# Sheet_1.net
KiCad netlist of a schematic drawn in EasyEDA
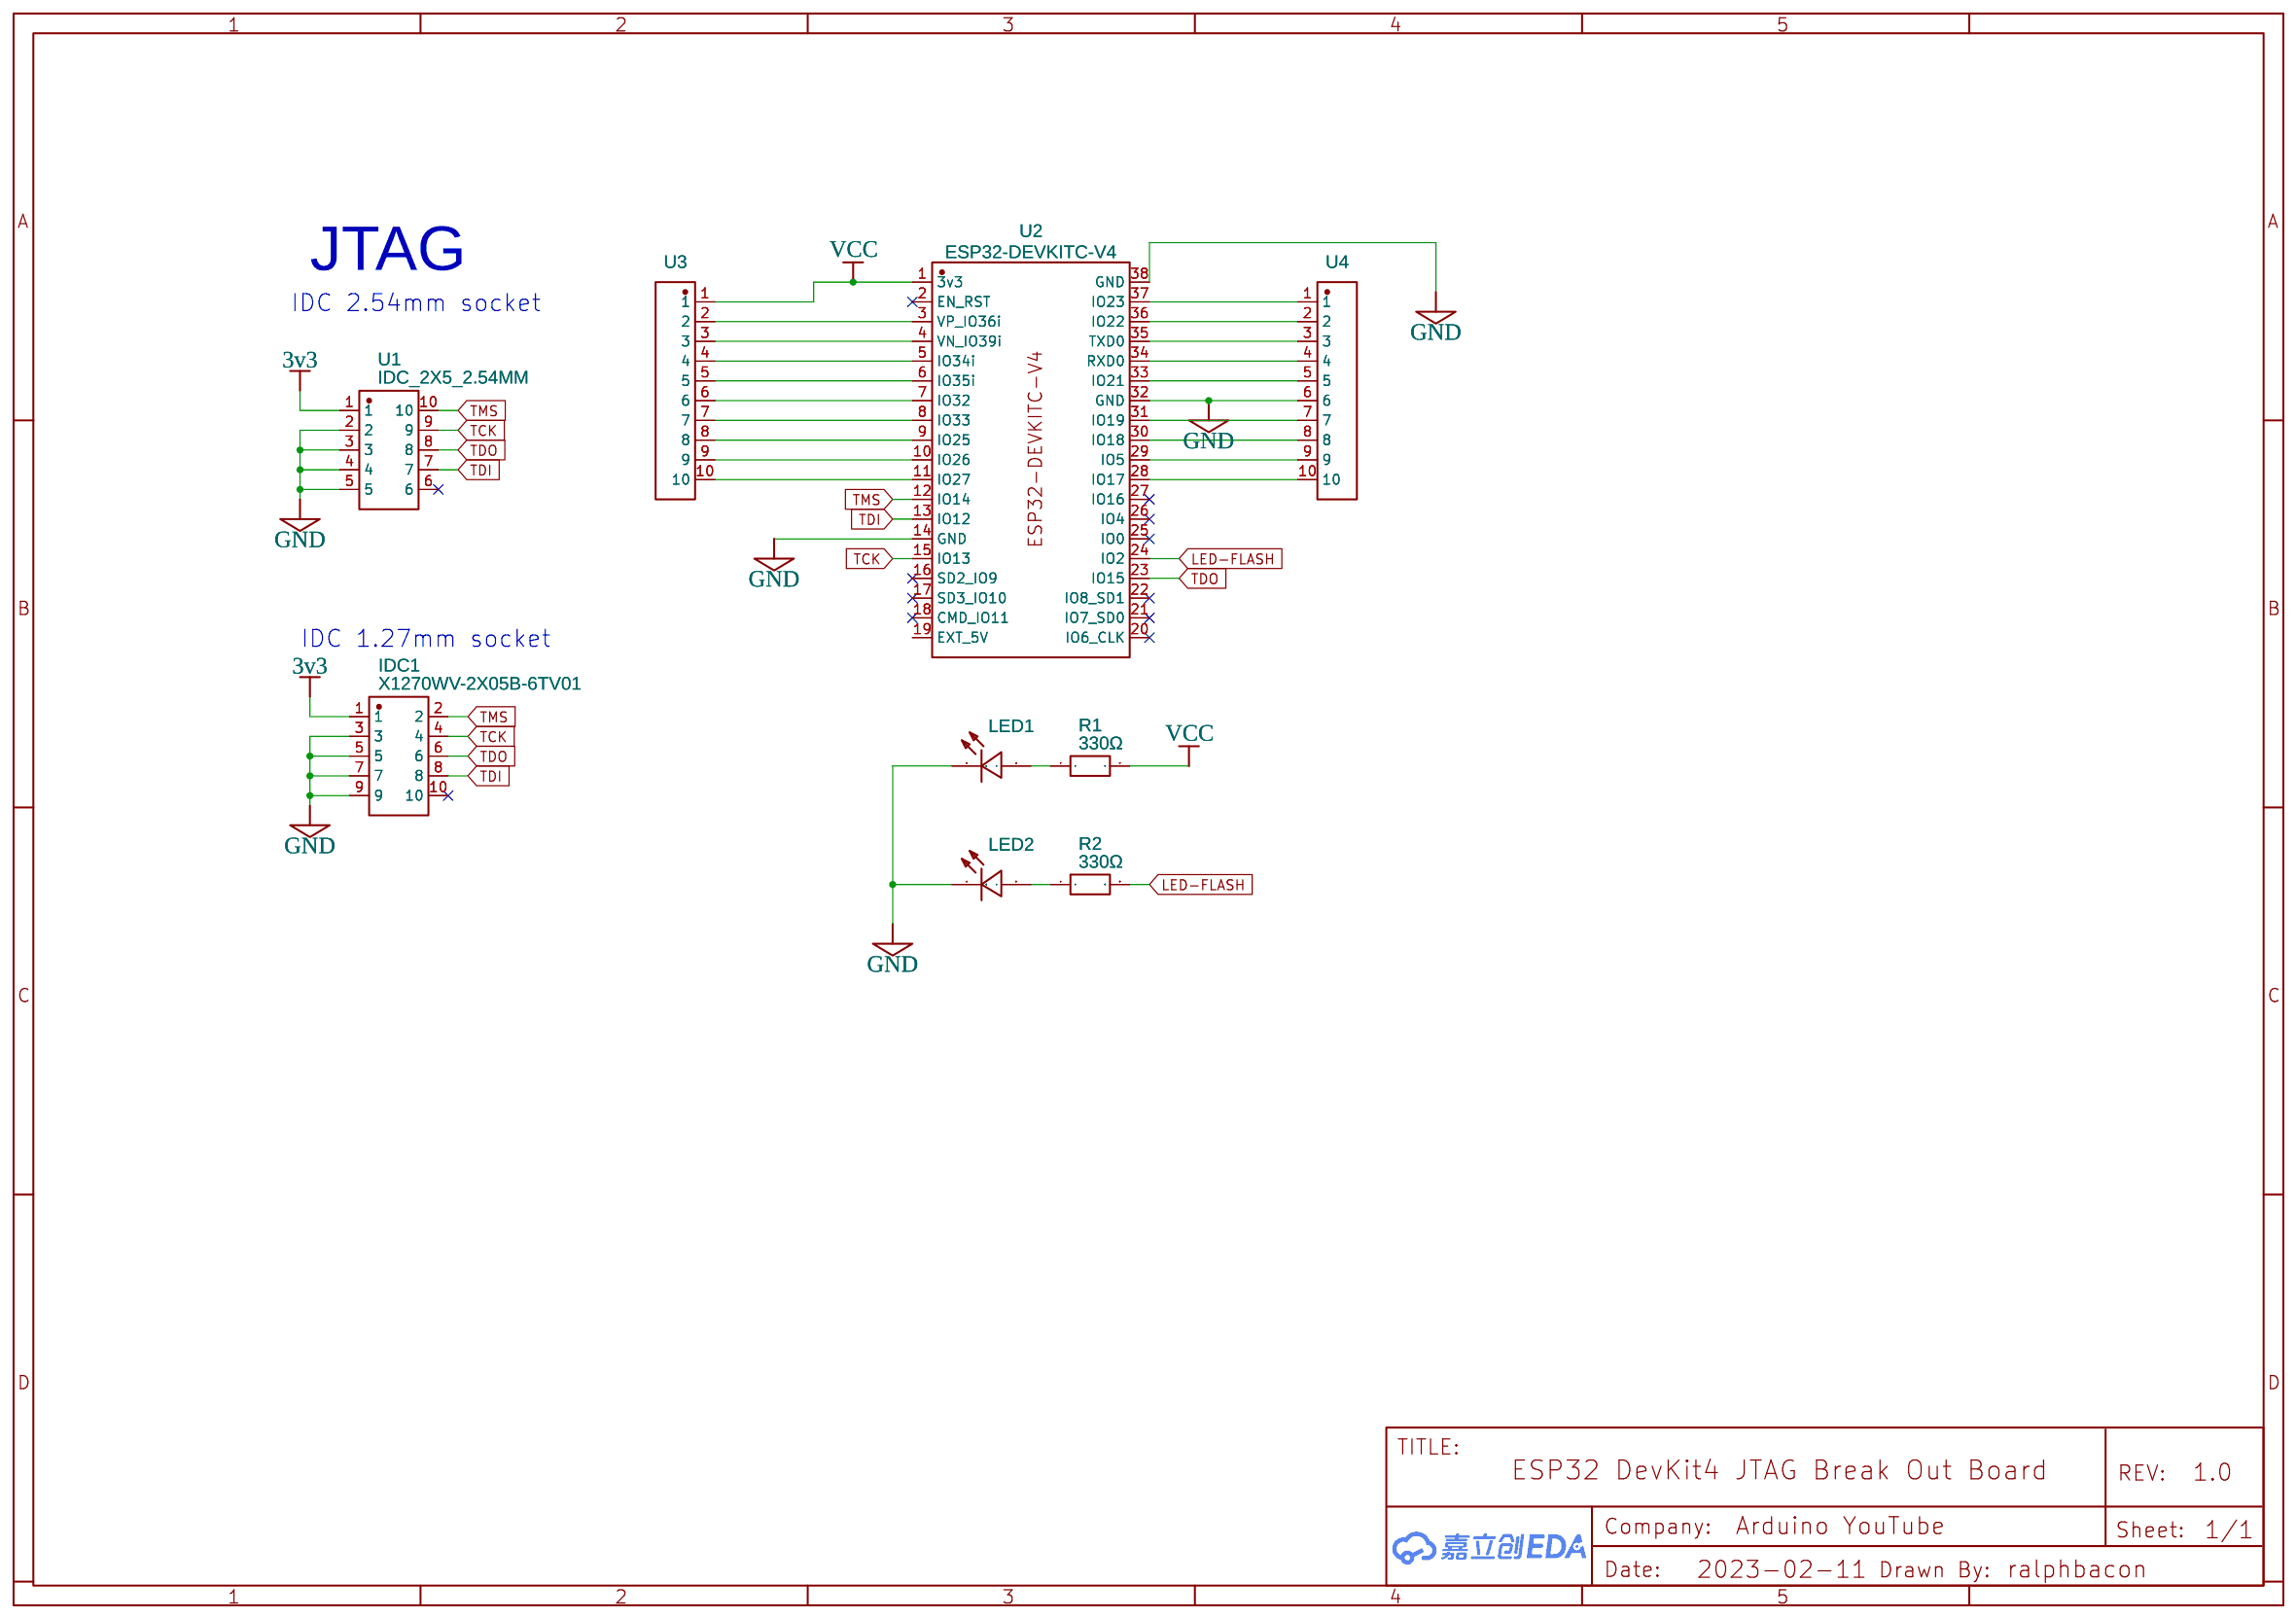
[diagram p0: schematic sheet]

(export (version "E")
  (design (tool "Eeschema 10.0.6"))
  (components
    (comp (ref "IDC1")
      (value "X1270WV-2X05B-6TV01")
      (fields
        (field (name "BOM_Manufacturer Part") "X1270WV-2x05B-6TV01")
        (field (name "BOM_Supplier Part") "C2962225")
      )
      (libsource (lib "") (part "X1270WV-2X05B-6TV01"))
    )
    (comp (ref "LED1")
      (value "SMDREDLED红色超高亮0805")
      (fields
        (field (name "BOM_Manufacturer Part") "SMDRedLED红色超高亮0805")
        (field (name "BOM_Supplier Part") "C9900019100")
      )
      (libsource (lib "") (part "SMDREDLED红色超高亮0805"))
    )
    (comp (ref "LED2")
      (value "SMDREDLED红色超高亮0805")
      (fields
        (field (name "BOM_Manufacturer Part") "SMDRedLED红色超高亮0805")
        (field (name "BOM_Supplier Part") "C9900019100")
      )
      (libsource (lib "") (part "SMDREDLED红色超高亮0805"))
    )
    (comp (ref "R1")
      (value "330Ω")
      (fields
        (field (name "BOM_Manufacturer Part") "RT0603DRD07330RL")
        (field (name "BOM_Supplier Part") "C723588")
      )
      (libsource (lib "") (part "RT0603DRD07330RL"))
    )
    (comp (ref "R2")
      (value "330Ω")
      (fields
        (field (name "BOM_Manufacturer Part") "RT0603DRD07330RL")
        (field (name "BOM_Supplier Part") "C723588")
      )
      (libsource (lib "") (part "RT0603DRD07330RL"))
    )
    (comp (ref "U1")
      (value "IDC_2X5_2.54MM")
      (fields
        (field (name "BOM_Manufacturer Part") "IDC_2x5_2.54mm")
        (field (name "BOM_Supplier Part") "C9900012100")
      )
      (libsource (lib "") (part "IDC_2X5_2.54MM"))
    )
    (comp (ref "U2") (value "ESP32-DEVKITC-V4") (libsource (lib "") (part "ESP32-DevKitC v4")))
    (comp (ref "U3")
      (value "间距2.54MM蓝色排母座1X10PIN")
      (fields
        (field (name "BOM_Manufacturer Part") "间距2.54mm蓝色排母座1x10pin")
        (field (name "BOM_Supplier Part") "C9900015505")
      )
      (libsource (lib "") (part "间距2.54MM蓝色排母座1X10PIN_1"))
    )
    (comp (ref "U4")
      (value "间距2.54MM蓝色排母座1X10PIN")
      (fields
        (field (name "BOM_Manufacturer Part") "间距2.54mm蓝色排母座1x10pin")
        (field (name "BOM_Supplier Part") "C9900015505")
      )
      (libsource (lib "") (part "间距2.54MM蓝色排母座1X10PIN"))
    )
  )
  (nets
    (net (code "1") (name "3v3") (class "Default")
      (node (ref "IDC1") (pin "1") (pinfunction "1_1") (pintype "unspecified"))
      (node (ref "U1") (pin "1") (pinfunction "1_1") (pintype "unspecified"))
    )
    (net (code "2") (name "GND") (class "Default")
      (node (ref "IDC1") (pin "3") (pinfunction "3_3") (pintype "unspecified"))
      (node (ref "IDC1") (pin "5") (pinfunction "5_5") (pintype "unspecified"))
      (node (ref "IDC1") (pin "7") (pinfunction "7_7") (pintype "unspecified"))
      (node (ref "IDC1") (pin "9") (pinfunction "9_9") (pintype "unspecified"))
      (node (ref "LED1") (pin "1") (pinfunction "C_1") (pintype "unspecified"))
      (node (ref "LED2") (pin "1") (pinfunction "C_1") (pintype "unspecified"))
      (node (ref "U1") (pin "2") (pinfunction "2_2") (pintype "unspecified"))
      (node (ref "U1") (pin "3") (pinfunction "3_3") (pintype "unspecified"))
      (node (ref "U1") (pin "4") (pinfunction "4_4") (pintype "unspecified"))
      (node (ref "U1") (pin "5") (pinfunction "5_5") (pintype "unspecified"))
      (node (ref "U2") (pin "14") (pinfunction "GND_14") (pintype "unspecified"))
      (node (ref "U2") (pin "32") (pinfunction "GND_32") (pintype "unspecified"))
      (node (ref "U2") (pin "38") (pinfunction "GND_38") (pintype "unspecified"))
      (node (ref "U4") (pin "6") (pinfunction "6_6") (pintype "unspecified"))
    )
    (net (code "3") (name "LED-FLASH") (class "Default")
      (node (ref "R2") (pin "2") (pinfunction "2_2") (pintype "unspecified"))
      (node (ref "U2") (pin "24") (pinfunction "IO2_24") (pintype "unspecified"))
    )
    (net (code "4") (name "Net-(LED1-A)") (class "Default")
      (node (ref "LED1") (pin "2") (pinfunction "A_2") (pintype "unspecified"))
      (node (ref "R1") (pin "1") (pinfunction "1_1") (pintype "unspecified"))
    )
    (net (code "5") (name "Net-(LED2-A)") (class "Default")
      (node (ref "LED2") (pin "2") (pinfunction "A_2") (pintype "unspecified"))
      (node (ref "R2") (pin "1") (pinfunction "1_1") (pintype "unspecified"))
    )
    (net (code "6") (name "Net-(U2-IO5)") (class "Default")
      (node (ref "U2") (pin "29") (pinfunction "IO5_29") (pintype "unspecified"))
      (node (ref "U4") (pin "9") (pinfunction "9_9") (pintype "unspecified"))
    )
    (net (code "7") (name "Net-(U2-IO17)") (class "Default")
      (node (ref "U2") (pin "28") (pinfunction "IO17_28") (pintype "unspecified"))
      (node (ref "U4") (pin "10") (pinfunction "10_10") (pintype "unspecified"))
    )
    (net (code "8") (name "Net-(U2-IO18)") (class "Default")
      (node (ref "U2") (pin "30") (pinfunction "IO18_30") (pintype "unspecified"))
      (node (ref "U4") (pin "8") (pinfunction "8_8") (pintype "unspecified"))
    )
    (net (code "9") (name "Net-(U2-IO19)") (class "Default")
      (node (ref "U2") (pin "31") (pinfunction "IO19_31") (pintype "unspecified"))
      (node (ref "U4") (pin "7") (pinfunction "7_7") (pintype "unspecified"))
    )
    (net (code "10") (name "Net-(U2-IO21)") (class "Default")
      (node (ref "U2") (pin "33") (pinfunction "IO21_33") (pintype "unspecified"))
      (node (ref "U4") (pin "5") (pinfunction "5_5") (pintype "unspecified"))
    )
    (net (code "11") (name "Net-(U2-IO22)") (class "Default")
      (node (ref "U2") (pin "36") (pinfunction "IO22_36") (pintype "unspecified"))
      (node (ref "U4") (pin "2") (pinfunction "2_2") (pintype "unspecified"))
    )
    (net (code "12") (name "Net-(U2-IO23)") (class "Default")
      (node (ref "U2") (pin "37") (pinfunction "IO23_37") (pintype "unspecified"))
      (node (ref "U4") (pin "1") (pinfunction "1_1") (pintype "unspecified"))
    )
    (net (code "13") (name "Net-(U2-IO25)") (class "Default")
      (node (ref "U2") (pin "9") (pinfunction "IO25_9") (pintype "unspecified"))
      (node (ref "U3") (pin "8") (pinfunction "8_8") (pintype "unspecified"))
    )
    (net (code "14") (name "Net-(U2-IO26)") (class "Default")
      (node (ref "U2") (pin "10") (pinfunction "IO26_10") (pintype "unspecified"))
      (node (ref "U3") (pin "9") (pinfunction "9_9") (pintype "unspecified"))
    )
    (net (code "15") (name "Net-(U2-IO27)") (class "Default")
      (node (ref "U2") (pin "11") (pinfunction "IO27_11") (pintype "unspecified"))
      (node (ref "U3") (pin "10") (pinfunction "10_10") (pintype "unspecified"))
    )
    (net (code "16") (name "Net-(U2-IO32)") (class "Default")
      (node (ref "U2") (pin "7") (pinfunction "IO32_7") (pintype "unspecified"))
      (node (ref "U3") (pin "6") (pinfunction "6_6") (pintype "unspecified"))
    )
    (net (code "17") (name "Net-(U2-IO33)") (class "Default")
      (node (ref "U2") (pin "8") (pinfunction "IO33_8") (pintype "unspecified"))
      (node (ref "U3") (pin "7") (pinfunction "7_7") (pintype "unspecified"))
    )
    (net (code "18") (name "Net-(U2-IO34i)") (class "Default")
      (node (ref "U2") (pin "5") (pinfunction "IO34i_5") (pintype "unspecified"))
      (node (ref "U3") (pin "4") (pinfunction "4_4") (pintype "unspecified"))
    )
    (net (code "19") (name "Net-(U2-IO35i)") (class "Default")
      (node (ref "U2") (pin "6") (pinfunction "IO35i_6") (pintype "unspecified"))
      (node (ref "U3") (pin "5") (pinfunction "5_5") (pintype "unspecified"))
    )
    (net (code "20") (name "Net-(U2-RXD0)") (class "Default")
      (node (ref "U2") (pin "34") (pinfunction "RXD0_34") (pintype "unspecified"))
      (node (ref "U4") (pin "4") (pinfunction "4_4") (pintype "unspecified"))
    )
    (net (code "21") (name "Net-(U2-TXD0)") (class "Default")
      (node (ref "U2") (pin "35") (pinfunction "TXD0_35") (pintype "unspecified"))
      (node (ref "U4") (pin "3") (pinfunction "3_3") (pintype "unspecified"))
    )
    (net (code "22") (name "Net-(U2-VN_IO39i)") (class "Default")
      (node (ref "U2") (pin "4") (pinfunction "VN_IO39i_4") (pintype "unspecified"))
      (node (ref "U3") (pin "3") (pinfunction "3_3") (pintype "unspecified"))
    )
    (net (code "23") (name "Net-(U2-VP_IO36i)") (class "Default")
      (node (ref "U2") (pin "3") (pinfunction "VP_IO36i_3") (pintype "unspecified"))
      (node (ref "U3") (pin "2") (pinfunction "2_2") (pintype "unspecified"))
    )
    (net (code "24") (name "TCK") (class "Default")
      (node (ref "IDC1") (pin "4") (pinfunction "4_4") (pintype "unspecified"))
      (node (ref "U1") (pin "9") (pinfunction "9_9") (pintype "unspecified"))
      (node (ref "U2") (pin "15") (pinfunction "IO13_15") (pintype "unspecified"))
    )
    (net (code "25") (name "TDI") (class "Default")
      (node (ref "IDC1") (pin "8") (pinfunction "8_8") (pintype "unspecified"))
      (node (ref "U1") (pin "7") (pinfunction "7_7") (pintype "unspecified"))
      (node (ref "U2") (pin "13") (pinfunction "IO12_13") (pintype "unspecified"))
    )
    (net (code "26") (name "TDO") (class "Default")
      (node (ref "IDC1") (pin "6") (pinfunction "6_6") (pintype "unspecified"))
      (node (ref "U1") (pin "8") (pinfunction "8_8") (pintype "unspecified"))
      (node (ref "U2") (pin "23") (pinfunction "IO15_23") (pintype "unspecified"))
    )
    (net (code "27") (name "TMS") (class "Default")
      (node (ref "IDC1") (pin "2") (pinfunction "2_2") (pintype "unspecified"))
      (node (ref "U1") (pin "10") (pinfunction "10_10") (pintype "unspecified"))
      (node (ref "U2") (pin "12") (pinfunction "IO14_12") (pintype "unspecified"))
    )
    (net (code "28") (name "VCC") (class "Default")
      (node (ref "R1") (pin "2") (pinfunction "2_2") (pintype "unspecified"))
      (node (ref "U2") (pin "1") (pinfunction "3v3_1") (pintype "unspecified"))
      (node (ref "U3") (pin "1") (pinfunction "1_1") (pintype "unspecified"))
    )
    (net (code "29") (name "unconnected-(IDC1-Pad10)") (class "Default")
      (node (ref "IDC1") (pin "10") (pinfunction "10_10") (pintype "unspecified+no_connect"))
    )
    (net (code "30") (name "unconnected-(U1-Pad6)") (class "Default")
      (node (ref "U1") (pin "6") (pinfunction "6_6") (pintype "unspecified+no_connect"))
    )
    (net (code "31") (name "unconnected-(U2-CMD_IO11-Pad18)") (class "Default")
      (node (ref "U2") (pin "18") (pinfunction "CMD_IO11_18") (pintype "unspecified+no_connect"))
    )
    (net (code "32") (name "unconnected-(U2-EN_RST-Pad2)") (class "Default")
      (node (ref "U2") (pin "2") (pinfunction "EN_RST_2") (pintype "unspecified+no_connect"))
    )
    (net (code "33") (name "unconnected-(U2-EXT_5V-Pad19)") (class "Default")
      (node (ref "U2") (pin "19") (pinfunction "EXT_5V_19") (pintype "unspecified"))
    )
    (net (code "34") (name "unconnected-(U2-IO0-Pad25)") (class "Default")
      (node (ref "U2") (pin "25") (pinfunction "IO0_25") (pintype "unspecified+no_connect"))
    )
    (net (code "35") (name "unconnected-(U2-IO4-Pad26)") (class "Default")
      (node (ref "U2") (pin "26") (pinfunction "IO4_26") (pintype "unspecified+no_connect"))
    )
    (net (code "36") (name "unconnected-(U2-IO6_CLK-Pad20)") (class "Default")
      (node (ref "U2") (pin "20") (pinfunction "IO6_CLK_20") (pintype "unspecified+no_connect"))
    )
    (net (code "37") (name "unconnected-(U2-IO7_SD0-Pad21)") (class "Default")
      (node (ref "U2") (pin "21") (pinfunction "IO7_SD0_21") (pintype "unspecified+no_connect"))
    )
    (net (code "38") (name "unconnected-(U2-IO8_SD1-Pad22)") (class "Default")
      (node (ref "U2") (pin "22") (pinfunction "IO8_SD1_22") (pintype "unspecified+no_connect"))
    )
    (net (code "39") (name "unconnected-(U2-IO16-Pad27)") (class "Default")
      (node (ref "U2") (pin "27") (pinfunction "IO16_27") (pintype "unspecified+no_connect"))
    )
    (net (code "40") (name "unconnected-(U2-SD2_IO9-Pad16)") (class "Default")
      (node (ref "U2") (pin "16") (pinfunction "SD2_IO9_16") (pintype "unspecified+no_connect"))
    )
    (net (code "41") (name "unconnected-(U2-SD3_IO10-Pad17)") (class "Default")
      (node (ref "U2") (pin "17") (pinfunction "SD3_IO10_17") (pintype "unspecified+no_connect"))
    )
  )
)
